# gpio.net
KiCad netlist of a schematic drawn in Altium Designer
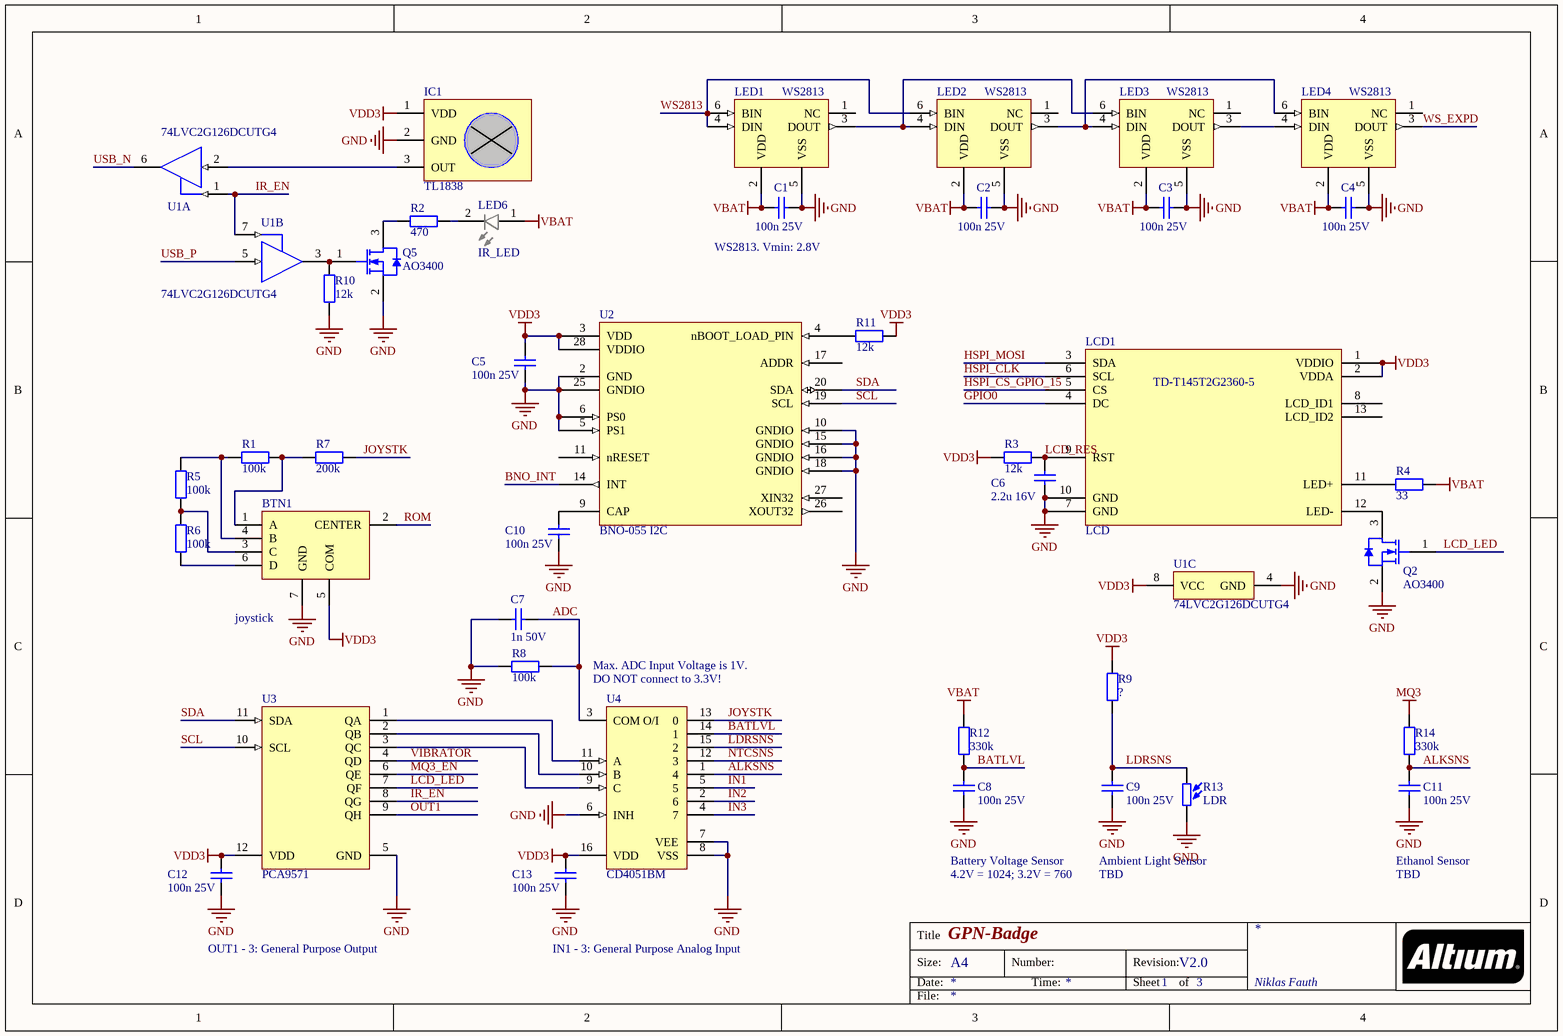
[diagram p0: gpio.SchDoc]

(export (version "E")
  (design (tool "Eeschema 10.0.6"))
  (components
    (comp (ref "BTN1")
      (value "joystick")
      (footprint "joystick")
      (libsource (lib "GPN–Badge") (part "joystick"))
    )
    (comp (ref "C1")
      (value "100n 25V")
      (footprint "C-0603-M")
      (description "Capacitor 100n 25V")
      (libsource (lib "Passives") (part "C-0603-100n-25V"))
    )
    (comp (ref "C2")
      (value "100n 25V")
      (footprint "C-0603-M")
      (description "Capacitor 100n 25V")
      (libsource (lib "Passives") (part "C-0603-100n-25V"))
    )
    (comp (ref "C3")
      (value "100n 25V")
      (footprint "C-0603-M")
      (description "Capacitor 100n 25V")
      (libsource (lib "Passives") (part "C-0603-100n-25V"))
    )
    (comp (ref "C4")
      (value "100n 25V")
      (footprint "C-0603-M")
      (description "Capacitor 100n 25V")
      (libsource (lib "Passives") (part "C-0603-100n-25V"))
    )
    (comp (ref "C5")
      (value "100n 25V")
      (footprint "C-0603-M")
      (description "Capacitor 100n 25V")
      (libsource (lib "Passives") (part "C-0603-100n-25V"))
    )
    (comp (ref "C6")
      (value "2.2u 16V")
      (footprint "C-0603-M")
      (description "Capacitor 2.2uF 16V")
      (libsource (lib "Passives") (part "C-0603-2u2-16V"))
    )
    (comp (ref "C7")
      (value "1n 50V")
      (footprint "C-0603-M")
      (description "Capacitor 1nF 50V")
      (libsource (lib "Passives") (part "C-0603-1n-50V"))
    )
    (comp (ref "C8")
      (value "100n 25V")
      (footprint "C-0603-M")
      (description "Capacitor 100n 25V")
      (libsource (lib "Passives") (part "C-0603-100n-25V"))
    )
    (comp (ref "C9")
      (value "100n 25V")
      (footprint "C-0603-M")
      (description "Capacitor 100n 25V")
      (libsource (lib "Passives") (part "C-0603-100n-25V"))
    )
    (comp (ref "C10")
      (value "100n 25V")
      (footprint "C-0603-M")
      (description "Capacitor 100n 25V")
      (libsource (lib "Passives") (part "C-0603-100n-25V"))
    )
    (comp (ref "C11")
      (value "100n 25V")
      (footprint "C-0603-M")
      (description "Capacitor 100n 25V")
      (libsource (lib "Passives") (part "C-0603-100n-25V"))
    )
    (comp (ref "C12")
      (value "100n 25V")
      (footprint "C-0603-M")
      (description "Capacitor 100n 25V")
      (libsource (lib "Passives") (part "C-0603-100n-25V"))
    )
    (comp (ref "C13")
      (value "100n 25V")
      (footprint "C-0603-M")
      (description "Capacitor 100n 25V")
      (libsource (lib "Passives") (part "C-0603-100n-25V"))
    )
    (comp (ref "IC1") (value "TL1838") (footprint "TL1838") (libsource (lib "gpn-badge") (part "TL1838")))
    (comp (ref "LCD1") (value "LCD") (footprint "LCD") (libsource (lib "GPN–Badge") (part "LCD")))
    (comp (ref "LED1")
      (value "WS2813")
      (footprint "plcc6")
      (description "WS2813 Addressable LED")
      (libsource (lib "advanced") (part "WS2813"))
    )
    (comp (ref "LED2")
      (value "WS2813")
      (footprint "plcc6")
      (description "WS2813 Addressable LED")
      (libsource (lib "advanced") (part "WS2813"))
    )
    (comp (ref "LED3")
      (value "WS2813")
      (footprint "plcc6")
      (description "WS2813 Addressable LED")
      (libsource (lib "advanced") (part "WS2813"))
    )
    (comp (ref "LED4")
      (value "WS2813")
      (footprint "plcc6")
      (description "WS2813 Addressable LED")
      (libsource (lib "advanced") (part "WS2813"))
    )
    (comp (ref "LED6") (value "IR_LED") (footprint "IR_LED") (libsource (lib "gpn-badge") (part "IR_LED")))
    (comp (ref "Q2")
      (value "AO3400")
      (footprint "AO-SOT23-3_V")
      (description "N-channel Enhancement Mode Field-Effect Transistor; 5.8A/30V")
      (fields (field (name "MANUFACTURER") "Alpha and Omega"))
      (libsource (lib "Altium Content Vault") (part "AO-NEMOS-G1S2D3-3"))
    )
    (comp (ref "Q5")
      (value "AO3400")
      (footprint "AO-SOT23-3_V")
      (description "N-channel Enhancement Mode Field-Effect Transistor; 5.8A/30V")
      (fields (field (name "MANUFACTURER") "Alpha and Omega"))
      (libsource (lib "Altium Content Vault") (part "AO-NEMOS-G1S2D3-3"))
    )
    (comp (ref "R1")
      (value "100k")
      (footprint "R-0603-M")
      (description "Resistor 100k")
      (libsource (lib "") (part "R-0603-100k_1"))
    )
    (comp (ref "R2")
      (value "470")
      (footprint "R-0603-M")
      (description "Resistor 470")
      (libsource (lib "Passives") (part "R-0603-470"))
    )
    (comp (ref "R3")
      (value "12k")
      (footprint "R-0603-M")
      (description "Resistor 12k")
      (libsource (lib "Passives") (part "R-0603-12k"))
    )
    (comp (ref "R4")
      (value "33")
      (footprint "R-0603-M")
      (description "Resistor 10")
      (libsource (lib "Passives") (part "R-0603-10"))
    )
    (comp (ref "R5")
      (value "100k")
      (footprint "R-0603-M")
      (description "Resistor 100k")
      (libsource (lib "Passives") (part "R-0603-100k"))
    )
    (comp (ref "R6")
      (value "100k")
      (footprint "R-0603-M")
      (description "Resistor 100k")
      (libsource (lib "Passives") (part "R-0603-100k"))
    )
    (comp (ref "R7")
      (value "200k")
      (footprint "R-0603-H")
      (description "Resistor 200k")
      (libsource (lib "Passives") (part "R-0603-200k"))
    )
    (comp (ref "R8")
      (value "100k")
      (footprint "R-0603-M")
      (description "Resistor 100k")
      (libsource (lib "") (part "R-0603-100k_1"))
    )
    (comp (ref "R9")
      (value "?")
      (footprint "R-0603-M")
      (description "Resistor 300k")
      (libsource (lib "Passives") (part "R-0603-300k"))
    )
    (comp (ref "R10")
      (value "12k")
      (footprint "R-0603-M")
      (description "Resistor 12k")
      (libsource (lib "gpn-badge") (part "R-0603-12k"))
    )
    (comp (ref "R11")
      (value "12k")
      (footprint "R-0603-M")
      (description "Resistor 12k")
      (libsource (lib "Passives") (part "R-0603-12k"))
    )
    (comp (ref "R12")
      (value "330k")
      (footprint "R-0603-M")
      (description "Resistor 300k")
      (libsource (lib "Passives") (part "R-0603-300k"))
    )
    (comp (ref "R13") (value "LDR") (footprint "LDR-5mm") (libsource (lib "gpn-badge") (part "LDR")))
    (comp (ref "R14")
      (value "330k")
      (footprint "R-0603-M")
      (description "Resistor 300k")
      (libsource (lib "Passives") (part "R-0603-300k"))
    )
    (comp (ref "U1")
      (value "74LVC2G126DCUTG4")
      (footprint "DCU0008A_L")
      (description "Dual Bus Buffer Gate With 3-State Outputs, DCU0008A, SMALL T&R")
      (fields
        (field (name "MANUFACTURER") "Texas Instruments")
        (field (name "GENERIC PART NUMBER") "SN74LVC2G126")
      )
      (libsource (lib "") (part "TI-SN74XXX2G126-8_A_1"))
    )
    (comp (ref "U2")
      (value "BNO-055 I2C")
      (footprint "BNO-055")
      (description "Bosch Sensortec 9-Axis motion fusion sensor")
      (libsource (lib "advanced") (part "BNO-055-I2C"))
    )
    (comp (ref "U3")
      (value "PCA9571")
      (footprint "SON40P210X100-10N")
      (description "I2C Port extender")
      (libsource (lib "gpn-badge") (part "PCA9571"))
    )
    (comp (ref "U4")
      (value "CD4051BM")
      (footprint "D0016A_M")
      (description "CMOS Single 8-Channel Analog Multiplexer/Demultiplexer with Logic-Level Conversion, D0016A, TUBE")
      (fields
        (field (name "MANUFACTURER") "Texas Instruments")
        (field (name "GENERIC PART NUMBER") "CD4051B")
      )
      (libsource (lib "Altium Content Vault") (part "CMP-1575-00043-4"))
    )
  )
  (nets
    (net (code "1") (name "/ADC") (class "Default")
      (node (ref "C7") (pin "2") (pinfunction "2_2") (pintype "passive"))
      (node (ref "R8") (pin "2") (pinfunction "2_2") (pintype "passive"))
      (node (ref "U4") (pin "3") (pinfunction "COM_O/I_3") (pintype "passive"))
    )
    (net (code "2") (name "/ALKSNS") (class "Default")
      (node (ref "C11") (pin "2") (pinfunction "2_2") (pintype "passive"))
      (node (ref "R14") (pin "1") (pinfunction "1_1") (pintype "passive"))
      (node (ref "U4") (pin "1") (pinfunction "4_1") (pintype "passive"))
    )
    (net (code "3") (name "/BATLVL") (class "Default")
      (node (ref "C8") (pin "2") (pinfunction "2_2") (pintype "passive"))
      (node (ref "R12") (pin "1") (pinfunction "1_1") (pintype "passive"))
      (node (ref "U4") (pin "14") (pinfunction "1_14") (pintype "passive"))
    )
    (net (code "4") (name "/BNO_INT") (class "Default")
      (node (ref "U2") (pin "14") (pinfunction "INT_14") (pintype "output"))
    )
    (net (code "5") (name "/GPIO0") (class "Default")
      (node (ref "LCD1") (pin "4") (pinfunction "DC_4") (pintype "passive"))
    )
    (net (code "6") (name "/HSPI_CLK") (class "Default")
      (node (ref "LCD1") (pin "6") (pinfunction "SCL_6") (pintype "passive"))
    )
    (net (code "7") (name "/HSPI_CS_GPIO_15") (class "Default")
      (node (ref "LCD1") (pin "5") (pinfunction "CS_5") (pintype "passive"))
    )
    (net (code "8") (name "/HSPI_MOSI") (class "Default")
      (node (ref "LCD1") (pin "3") (pinfunction "SDA_3") (pintype "passive"))
    )
    (net (code "9") (name "/IN1") (class "Default")
      (node (ref "U4") (pin "5") (pinfunction "5_5") (pintype "passive"))
    )
    (net (code "10") (name "/IN2") (class "Default")
      (node (ref "U4") (pin "2") (pinfunction "6_2") (pintype "passive"))
    )
    (net (code "11") (name "/IN3") (class "Default")
      (node (ref "U4") (pin "4") (pinfunction "7_4") (pintype "passive"))
    )
    (net (code "12") (name "/IR_EN") (class "Default")
      (node (ref "U1") (pin "1") (pinfunction "1OE_1") (pintype "input"))
      (node (ref "U1") (pin "7") (pinfunction "2OE_7") (pintype "input"))
      (node (ref "U3") (pin "8") (pinfunction "QG_8") (pintype "tri_state"))
    )
    (net (code "13") (name "/JOYSTK") (class "Default")
      (node (ref "R7") (pin "1") (pinfunction "1_1") (pintype "passive"))
      (node (ref "U4") (pin "13") (pinfunction "0_13") (pintype "passive"))
    )
    (net (code "14") (name "/LCD_LED") (class "Default")
      (node (ref "Q2") (pin "1") (pinfunction "G_1") (pintype "passive"))
      (node (ref "U3") (pin "7") (pinfunction "QF_7") (pintype "tri_state"))
    )
    (net (code "15") (name "/LCD_RES") (class "Default")
      (node (ref "C6") (pin "2") (pinfunction "2_2") (pintype "passive"))
      (node (ref "LCD1") (pin "9") (pinfunction "RST_9") (pintype "passive"))
      (node (ref "R3") (pin "2") (pinfunction "2_2") (pintype "passive"))
    )
    (net (code "16") (name "/LDRSNS") (class "Default")
      (node (ref "C9") (pin "2") (pinfunction "2_2") (pintype "passive"))
      (node (ref "R13") (pin "1") (pintype "passive"))
      (node (ref "R9") (pin "1") (pinfunction "1_1") (pintype "passive"))
      (node (ref "U4") (pin "15") (pinfunction "2_15") (pintype "passive"))
    )
    (net (code "17") (name "/MQ3_EN") (class "Default")
      (node (ref "U3") (pin "6") (pinfunction "QE_6") (pintype "tri_state"))
    )
    (net (code "18") (name "/NTCSNS") (class "Default")
      (node (ref "U4") (pin "12") (pinfunction "3_12") (pintype "passive"))
    )
    (net (code "19") (name "/OUT1") (class "Default")
      (node (ref "U3") (pin "9") (pinfunction "QH_9") (pintype "tri_state"))
    )
    (net (code "20") (name "/ROM") (class "Default")
      (node (ref "BTN1") (pin "2") (pinfunction "CENTER_2") (pintype "passive"))
    )
    (net (code "21") (name "/SCL") (class "Default")
      (node (ref "U2") (pin "19") (pinfunction "SCL_19") (pintype "input"))
      (node (ref "U3") (pin "10") (pinfunction "SCL_10") (pintype "input"))
    )
    (net (code "22") (name "/SDA") (class "Default")
      (node (ref "U2") (pin "20") (pinfunction "SDA_20") (pintype "bidirectional"))
      (node (ref "U3") (pin "11") (pinfunction "SDA_11") (pintype "input"))
    )
    (net (code "23") (name "/USB_N") (class "Default")
      (node (ref "U1") (pin "6") (pinfunction "1Y_6") (pintype "tri_state"))
    )
    (net (code "24") (name "/USB_P") (class "Default")
      (node (ref "U1") (pin "5") (pinfunction "2A_5") (pintype "input"))
    )
    (net (code "25") (name "/VIBRATOR") (class "Default")
      (node (ref "U3") (pin "4") (pinfunction "QD_4") (pintype "tri_state"))
    )
    (net (code "26") (name "/WS2813") (class "Default")
      (node (ref "LED1") (pin "4") (pinfunction "DIN_4") (pintype "input"))
      (node (ref "LED1") (pin "6") (pinfunction "BIN_6") (pintype "input"))
      (node (ref "LED2") (pin "6") (pinfunction "BIN_6") (pintype "input"))
    )
    (net (code "27") (name "/WS_EXPD") (class "Default")
      (node (ref "LED4") (pin "3") (pinfunction "DOUT_3") (pintype "output"))
    )
    (net (code "28") (name "GND") (class "Default")
      (node (ref "BTN1") (pin "7") (pinfunction "GND_7") (pintype "passive"))
      (node (ref "C1") (pin "1") (pinfunction "1_1") (pintype "passive"))
      (node (ref "C10") (pin "1") (pinfunction "1_1") (pintype "passive"))
      (node (ref "C11") (pin "1") (pinfunction "1_1") (pintype "passive"))
      (node (ref "C12") (pin "1") (pinfunction "1_1") (pintype "passive"))
      (node (ref "C13") (pin "1") (pinfunction "1_1") (pintype "passive"))
      (node (ref "C2") (pin "1") (pinfunction "1_1") (pintype "passive"))
      (node (ref "C3") (pin "1") (pinfunction "1_1") (pintype "passive"))
      (node (ref "C4") (pin "1") (pinfunction "1_1") (pintype "passive"))
      (node (ref "C5") (pin "1") (pinfunction "1_1") (pintype "passive"))
      (node (ref "C6") (pin "1") (pinfunction "1_1") (pintype "passive"))
      (node (ref "C7") (pin "1") (pinfunction "1_1") (pintype "passive"))
      (node (ref "C8") (pin "1") (pinfunction "1_1") (pintype "passive"))
      (node (ref "C9") (pin "1") (pinfunction "1_1") (pintype "passive"))
      (node (ref "IC1") (pin "2") (pinfunction "GND_2") (pintype "passive"))
      (node (ref "LCD1") (pin "10") (pinfunction "GND_10") (pintype "passive"))
      (node (ref "LCD1") (pin "7") (pinfunction "GND_7") (pintype "passive"))
      (node (ref "LED1") (pin "5") (pinfunction "VSS_5") (pintype "power_in"))
      (node (ref "LED2") (pin "5") (pinfunction "VSS_5") (pintype "power_in"))
      (node (ref "LED3") (pin "5") (pinfunction "VSS_5") (pintype "power_in"))
      (node (ref "LED4") (pin "5") (pinfunction "VSS_5") (pintype "power_in"))
      (node (ref "Q2") (pin "2") (pinfunction "S_2") (pintype "passive"))
      (node (ref "Q5") (pin "2") (pinfunction "S_2") (pintype "passive"))
      (node (ref "R10") (pin "1") (pinfunction "1_1") (pintype "passive"))
      (node (ref "R13") (pin "2") (pintype "passive"))
      (node (ref "R8") (pin "1") (pinfunction "1_1") (pintype "passive"))
      (node (ref "U1") (pin "4") (pinfunction "GND_4") (pintype "power_in"))
      (node (ref "U2") (pin "10") (pinfunction "GNDIO_10") (pintype "input"))
      (node (ref "U2") (pin "15") (pinfunction "GNDIO_15") (pintype "input"))
      (node (ref "U2") (pin "16") (pinfunction "GNDIO_16") (pintype "input"))
      (node (ref "U2") (pin "18") (pinfunction "GNDIO_18") (pintype "input"))
      (node (ref "U2") (pin "2") (pinfunction "GND_2") (pintype "power_in"))
      (node (ref "U2") (pin "25") (pinfunction "GNDIO_25") (pintype "power_in"))
      (node (ref "U2") (pin "5") (pinfunction "PS1_5") (pintype "input"))
      (node (ref "U2") (pin "6") (pinfunction "PS0_6") (pintype "input"))
      (node (ref "U3") (pin "5") (pinfunction "GND_5") (pintype "power_in"))
      (node (ref "U4") (pin "6") (pinfunction "INH_6") (pintype "input"))
      (node (ref "U4") (pin "7") (pinfunction "VEE_7") (pintype "power_in"))
      (node (ref "U4") (pin "8") (pinfunction "VSS_8") (pintype "power_in"))
    )
    (net (code "29") (name "MQ3") (class "Default")
      (node (ref "R14") (pin "2") (pinfunction "2_2") (pintype "passive"))
    )
    (net (code "30") (name "Net-(BTN1-A)") (class "Default")
      (node (ref "BTN1") (pin "1") (pinfunction "A_1") (pintype "passive"))
      (node (ref "R1") (pin "2") (pinfunction "2_2") (pintype "passive"))
      (node (ref "R7") (pin "2") (pinfunction "2_2") (pintype "passive"))
    )
    (net (code "31") (name "Net-(BTN1-B)") (class "Default")
      (node (ref "BTN1") (pin "4") (pinfunction "B_4") (pintype "passive"))
      (node (ref "R1") (pin "1") (pinfunction "1_1") (pintype "passive"))
      (node (ref "R5") (pin "2") (pinfunction "2_2") (pintype "passive"))
    )
    (net (code "32") (name "Net-(BTN1-C)") (class "Default")
      (node (ref "BTN1") (pin "3") (pinfunction "C_3") (pintype "passive"))
      (node (ref "R5") (pin "1") (pinfunction "1_1") (pintype "passive"))
      (node (ref "R6") (pin "2") (pinfunction "2_2") (pintype "passive"))
    )
    (net (code "33") (name "Net-(BTN1-D)") (class "Default")
      (node (ref "BTN1") (pin "6") (pinfunction "D_6") (pintype "passive"))
      (node (ref "R6") (pin "1") (pinfunction "1_1") (pintype "passive"))
    )
    (net (code "34") (name "Net-(IC1-OUT)") (class "Default")
      (node (ref "IC1") (pin "3") (pinfunction "OUT_3") (pintype "passive"))
      (node (ref "U1") (pin "2") (pinfunction "1A_2") (pintype "input"))
    )
    (net (code "35") (name "Net-(LCD1-LED+)") (class "Default")
      (node (ref "LCD1") (pin "11") (pinfunction "LED+_11") (pintype "passive"))
      (node (ref "R4") (pin "1") (pinfunction "1_1") (pintype "passive"))
    )
    (net (code "36") (name "Net-(LCD1-LED-)") (class "Default")
      (node (ref "LCD1") (pin "12") (pinfunction "LED-_12") (pintype "passive"))
      (node (ref "Q2") (pin "3") (pinfunction "D_3") (pintype "passive"))
    )
    (net (code "37") (name "Net-(LED1-DOUT)") (class "Default")
      (node (ref "LED1") (pin "3") (pinfunction "DOUT_3") (pintype "output"))
      (node (ref "LED2") (pin "4") (pinfunction "DIN_4") (pintype "input"))
      (node (ref "LED3") (pin "6") (pinfunction "BIN_6") (pintype "input"))
    )
    (net (code "38") (name "Net-(LED2-DOUT)") (class "Default")
      (node (ref "LED2") (pin "3") (pinfunction "DOUT_3") (pintype "output"))
      (node (ref "LED3") (pin "4") (pinfunction "DIN_4") (pintype "input"))
      (node (ref "LED4") (pin "6") (pinfunction "BIN_6") (pintype "input"))
    )
    (net (code "39") (name "Net-(LED3-DOUT)") (class "Default")
      (node (ref "LED3") (pin "3") (pinfunction "DOUT_3") (pintype "output"))
      (node (ref "LED4") (pin "4") (pinfunction "DIN_4") (pintype "input"))
    )
    (net (code "40") (name "Net-(LED6-K)") (class "Default")
      (node (ref "LED6") (pin "2") (pinfunction "K_2") (pintype "passive"))
      (node (ref "R2") (pin "2") (pinfunction "2_2") (pintype "passive"))
    )
    (net (code "41") (name "Net-(Q5-D)") (class "Default")
      (node (ref "Q5") (pin "3") (pinfunction "D_3") (pintype "passive"))
      (node (ref "R2") (pin "1") (pinfunction "1_1") (pintype "passive"))
    )
    (net (code "42") (name "Net-(Q5-G)") (class "Default")
      (node (ref "Q5") (pin "1") (pinfunction "G_1") (pintype "passive"))
      (node (ref "R10") (pin "2") (pinfunction "2_2") (pintype "passive"))
      (node (ref "U1") (pin "3") (pinfunction "2Y_3") (pintype "tri_state"))
    )
    (net (code "43") (name "Net-(U2-CAP)") (class "Default")
      (node (ref "C10") (pin "2") (pinfunction "2_2") (pintype "passive"))
      (node (ref "U2") (pin "9") (pinfunction "CAP_9") (pintype "passive"))
    )
    (net (code "44") (name "Net-(U2-nBOOT_LOAD_PIN)") (class "Default")
      (node (ref "R11") (pin "1") (pinfunction "1_1") (pintype "passive"))
      (node (ref "U2") (pin "4") (pinfunction "nBOOT_LOAD_PIN_4") (pintype "input"))
    )
    (net (code "45") (name "Net-(U3-QA)") (class "Default")
      (node (ref "U3") (pin "1") (pinfunction "QA_1") (pintype "tri_state"))
      (node (ref "U4") (pin "11") (pinfunction "A_11") (pintype "input"))
    )
    (net (code "46") (name "Net-(U3-QB)") (class "Default")
      (node (ref "U3") (pin "2") (pinfunction "QB_2") (pintype "tri_state"))
      (node (ref "U4") (pin "10") (pinfunction "B_10") (pintype "input"))
    )
    (net (code "47") (name "Net-(U3-QC)") (class "Default")
      (node (ref "U3") (pin "3") (pinfunction "QC_3") (pintype "tri_state"))
      (node (ref "U4") (pin "9") (pinfunction "C_9") (pintype "input"))
    )
    (net (code "48") (name "VBAT") (class "Default")
      (node (ref "C1") (pin "2") (pinfunction "2_2") (pintype "passive"))
      (node (ref "C2") (pin "2") (pinfunction "2_2") (pintype "passive"))
      (node (ref "C3") (pin "2") (pinfunction "2_2") (pintype "passive"))
      (node (ref "C4") (pin "2") (pinfunction "2_2") (pintype "passive"))
      (node (ref "LED1") (pin "2") (pinfunction "VDD_2") (pintype "power_in"))
      (node (ref "LED2") (pin "2") (pinfunction "VDD_2") (pintype "power_in"))
      (node (ref "LED3") (pin "2") (pinfunction "VDD_2") (pintype "power_in"))
      (node (ref "LED4") (pin "2") (pinfunction "VDD_2") (pintype "power_in"))
      (node (ref "LED6") (pin "1") (pinfunction "A_1") (pintype "passive"))
      (node (ref "R12") (pin "2") (pinfunction "2_2") (pintype "passive"))
      (node (ref "R4") (pin "2") (pinfunction "2_2") (pintype "passive"))
    )
    (net (code "49") (name "VDD3") (class "Default")
      (node (ref "BTN1") (pin "5") (pinfunction "COM_5") (pintype "passive"))
      (node (ref "C12") (pin "2") (pinfunction "2_2") (pintype "passive"))
      (node (ref "C13") (pin "2") (pinfunction "2_2") (pintype "passive"))
      (node (ref "C5") (pin "2") (pinfunction "2_2") (pintype "passive"))
      (node (ref "IC1") (pin "1") (pinfunction "VDD_1") (pintype "passive"))
      (node (ref "LCD1") (pin "1") (pinfunction "VDDIO_1") (pintype "passive"))
      (node (ref "LCD1") (pin "2") (pinfunction "VDDA_2") (pintype "passive"))
      (node (ref "R11") (pin "2") (pinfunction "2_2") (pintype "passive"))
      (node (ref "R3") (pin "1") (pinfunction "1_1") (pintype "passive"))
      (node (ref "R9") (pin "2") (pinfunction "2_2") (pintype "passive"))
      (node (ref "U1") (pin "8") (pinfunction "VCC_8") (pintype "power_in"))
      (node (ref "U2") (pin "28") (pinfunction "VDDIO_28") (pintype "power_in"))
      (node (ref "U2") (pin "3") (pinfunction "VDD_3") (pintype "power_in"))
      (node (ref "U3") (pin "12") (pinfunction "VDD_12") (pintype "power_in"))
      (node (ref "U4") (pin "16") (pinfunction "VDD_16") (pintype "power_in"))
    )
    (net (code "50") (name "unconnected-(LCD1-LCD_ID1-Pad8)") (class "Default")
      (node (ref "LCD1") (pin "8") (pinfunction "LCD_ID1_8") (pintype "passive"))
    )
    (net (code "51") (name "unconnected-(LCD1-LCD_ID2-Pad13)") (class "Default")
      (node (ref "LCD1") (pin "13") (pinfunction "LCD_ID2_13") (pintype "passive"))
    )
    (net (code "52") (name "unconnected-(LED1-NC-Pad1)") (class "Default")
      (node (ref "LED1") (pin "1") (pinfunction "NC_1") (pintype "passive"))
    )
    (net (code "53") (name "unconnected-(LED2-NC-Pad1)") (class "Default")
      (node (ref "LED2") (pin "1") (pinfunction "NC_1") (pintype "passive"))
    )
    (net (code "54") (name "unconnected-(LED3-NC-Pad1)") (class "Default")
      (node (ref "LED3") (pin "1") (pinfunction "NC_1") (pintype "passive"))
    )
    (net (code "55") (name "unconnected-(LED4-NC-Pad1)") (class "Default")
      (node (ref "LED4") (pin "1") (pinfunction "NC_1") (pintype "passive"))
    )
    (net (code "56") (name "unconnected-(U2-ADDR-Pad17)") (class "Default")
      (node (ref "U2") (pin "17") (pinfunction "ADDR_17") (pintype "input"))
    )
    (net (code "57") (name "unconnected-(U2-XIN32-Pad27)") (class "Default")
      (node (ref "U2") (pin "27") (pinfunction "XIN32_27") (pintype "input"))
    )
    (net (code "58") (name "unconnected-(U2-XOUT32-Pad26)") (class "Default")
      (node (ref "U2") (pin "26") (pinfunction "XOUT32_26") (pintype "output"))
    )
    (net (code "59") (name "unconnected-(U2-nRESET-Pad11)") (class "Default")
      (node (ref "U2") (pin "11") (pinfunction "nRESET_11") (pintype "input"))
    )
  )
)
